# debug.net
KiCad netlist of a schematic drawn in Altium Designer
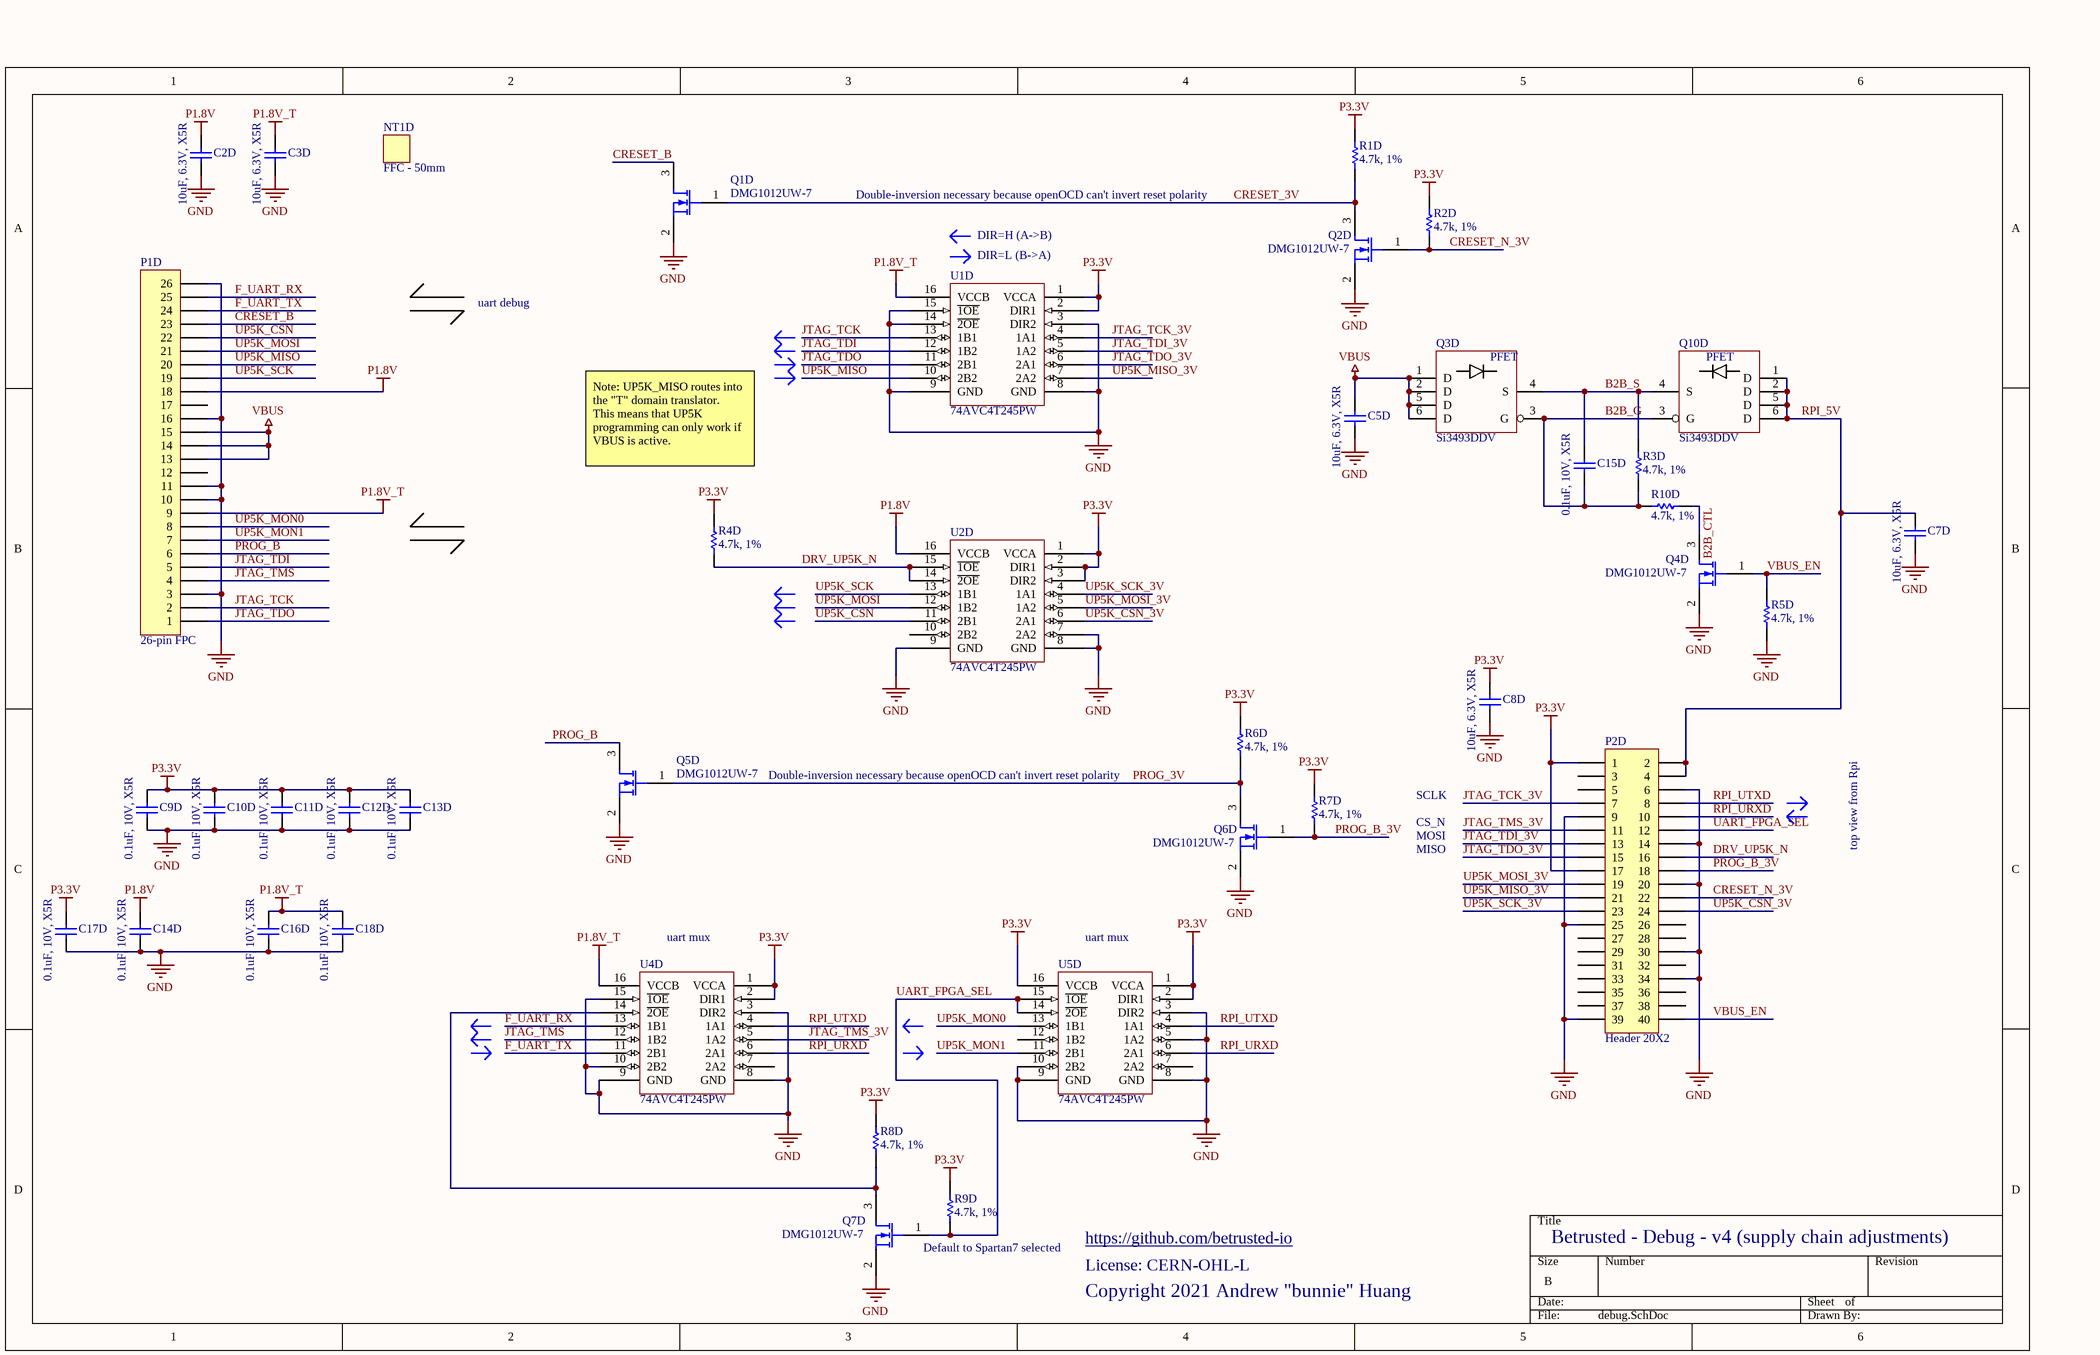
[diagram p0: debug.SchDoc]

(export (version "E")
  (design (tool "Eeschema 10.0.6"))
  (components
    (comp (ref "C2D")
      (value "10uF, 6.3V, X5R")
      (footprint "B_CAP0603")
      (description "Capacitor (Semiconductor SIM Model)")
      (fields (field (name "MPN") "CL10A106MQ8NNNC"))
      (libsource (lib "Miscellaneous Devices") (part "Cap Semi"))
    )
    (comp (ref "C3D")
      (value "10uF, 6.3V, X5R")
      (footprint "B_CAP0603")
      (description "Capacitor (Semiconductor SIM Model)")
      (fields (field (name "MPN") "CL10A106MQ8NNNC"))
      (libsource (lib "Miscellaneous Devices") (part "Cap Semi"))
    )
    (comp (ref "C5D")
      (value "10uF, 6.3V, X5R")
      (footprint "B_CAP0603")
      (description "Capacitor (Semiconductor SIM Model)")
      (fields (field (name "MPN") "CL10A106MQ8NNNC"))
      (libsource (lib "Miscellaneous Devices") (part "Cap Semi"))
    )
    (comp (ref "C7D")
      (value "10uF, 6.3V, X5R")
      (footprint "B_CAP0603")
      (description "Capacitor (Semiconductor SIM Model)")
      (fields (field (name "MPN") "CL10A106MQ8NNNC"))
      (libsource (lib "Miscellaneous Devices") (part "Cap Semi"))
    )
    (comp (ref "C8D")
      (value "10uF, 6.3V, X5R")
      (footprint "B_CAP0603")
      (description "Capacitor (Semiconductor SIM Model)")
      (fields (field (name "MPN") "CL10A106MQ8NNNC"))
      (libsource (lib "Miscellaneous Devices") (part "Cap Semi"))
    )
    (comp (ref "C9D")
      (value "0.1uF, 10V, X5R")
      (footprint "B_CAP0402")
      (description "Capacitor (Semiconductor SIM Model)")
      (fields (field (name "MPN") "CL05A104KP5NNNC"))
      (libsource (lib "Miscellaneous Devices") (part "Cap Semi"))
    )
    (comp (ref "C10D")
      (value "0.1uF, 10V, X5R")
      (footprint "B_CAP0402")
      (description "Capacitor (Semiconductor SIM Model)")
      (fields (field (name "MPN") "CL05A104KP5NNNC"))
      (libsource (lib "Miscellaneous Devices") (part "Cap Semi"))
    )
    (comp (ref "C11D")
      (value "0.1uF, 10V, X5R")
      (footprint "B_CAP0402")
      (description "Capacitor (Semiconductor SIM Model)")
      (fields (field (name "MPN") "CL05A104KP5NNNC"))
      (libsource (lib "Miscellaneous Devices") (part "Cap Semi"))
    )
    (comp (ref "C12D")
      (value "0.1uF, 10V, X5R")
      (footprint "B_CAP0402")
      (description "Capacitor (Semiconductor SIM Model)")
      (fields (field (name "MPN") "CL05A104KP5NNNC"))
      (libsource (lib "Miscellaneous Devices") (part "Cap Semi"))
    )
    (comp (ref "C13D")
      (value "0.1uF, 10V, X5R")
      (footprint "B_CAP0402")
      (description "Capacitor (Semiconductor SIM Model)")
      (fields (field (name "MPN") "CL05A104KP5NNNC"))
      (libsource (lib "Miscellaneous Devices") (part "Cap Semi"))
    )
    (comp (ref "C14D")
      (value "0.1uF, 10V, X5R")
      (footprint "B_CAP0402")
      (description "Capacitor (Semiconductor SIM Model)")
      (fields (field (name "MPN") "CL05A104KP5NNNC"))
      (libsource (lib "Miscellaneous Devices") (part "Cap Semi"))
    )
    (comp (ref "C15D")
      (value "0.1uF, 10V, X5R")
      (footprint "B_CAP0402")
      (description "Capacitor (Semiconductor SIM Model)")
      (fields (field (name "MPN") "CL05A104KP5NNNC"))
      (libsource (lib "Miscellaneous Devices") (part "Cap Semi"))
    )
    (comp (ref "C16D")
      (value "0.1uF, 10V, X5R")
      (footprint "B_CAP0402")
      (description "Capacitor (Semiconductor SIM Model)")
      (fields (field (name "MPN") "CL05A104KP5NNNC"))
      (libsource (lib "Miscellaneous Devices") (part "Cap Semi"))
    )
    (comp (ref "C17D")
      (value "0.1uF, 10V, X5R")
      (footprint "B_CAP0402")
      (description "Capacitor (Semiconductor SIM Model)")
      (fields (field (name "MPN") "CL05A104KP5NNNC"))
      (libsource (lib "Miscellaneous Devices") (part "Cap Semi"))
    )
    (comp (ref "C18D")
      (value "0.1uF, 10V, X5R")
      (footprint "B_CAP0402")
      (description "Capacitor (Semiconductor SIM Model)")
      (fields (field (name "MPN") "CL05A104KP5NNNC"))
      (libsource (lib "Miscellaneous Devices") (part "Cap Semi"))
    )
    (comp (ref "NT1D")
      (value "FFC - 50mm")
      (description "Placeholder for non-board BOM items")
      (fields (field (name "MPN") "FJH-26-D-02.00-4"))
      (libsource (lib "commonsch") (part "NOTE"))
    )
    (comp (ref "P1D")
      (value "26-pin FPC")
      (footprint "HRS_FH34SRJ-26S-0.5SH(50)")
      (description "26 Pin FPC header")
      (fields (field (name "MPN") "FH34SRJ-26S-0.5SH(99)"))
      (libsource (lib "commonsch-new") (part "FPC-26"))
    )
    (comp (ref "P2D")
      (value "Header 20X2")
      (footprint "SAMTEC_SSW-120-01-F-D")
      (description "Header, 20-Pin, Dual row")
      (fields (field (name "MPN") "CS25402-40G-S85-C") (field (name "PUBLISHER") "Altium Limited"))
      (libsource (lib "Miscellaneous Connectors") (part "Header 20X2"))
    )
    (comp (ref "Q1D")
      (value "DMG1012UW-7")
      (footprint "SOT323-3AN")
      (description "N-Channel MOSFET")
      (fields (field (name "PUBLISHER") "Altium Limited"))
      (libsource (lib "Miscellaneous Devices") (part "MOSFET-N"))
    )
    (comp (ref "Q2D")
      (value "DMG1012UW-7")
      (footprint "SOT323-3AN")
      (description "N-Channel MOSFET")
      (fields (field (name "PUBLISHER") "Altium Limited"))
      (libsource (lib "Miscellaneous Devices") (part "MOSFET-N"))
    )
    (comp (ref "Q3D")
      (value "Si3493DDV")
      (footprint "SOT26A-6N")
      (description "P-channel 20V 8A 32mOhm @ -2.5V")
      (fields (field (name "MPN") "SI3493DDV-T1-GE3"))
      (libsource (lib "") (part "Si3493DDV_1"))
    )
    (comp (ref "Q4D")
      (value "DMG1012UW-7")
      (footprint "SOT323-3AN")
      (description "N-Channel MOSFET")
      (fields (field (name "PUBLISHER") "Altium Limited"))
      (libsource (lib "Miscellaneous Devices") (part "MOSFET-N"))
    )
    (comp (ref "Q5D")
      (value "DMG1012UW-7")
      (footprint "SOT323-3AN")
      (description "N-Channel MOSFET")
      (fields (field (name "PUBLISHER") "Altium Limited"))
      (libsource (lib "Miscellaneous Devices") (part "MOSFET-N"))
    )
    (comp (ref "Q6D")
      (value "DMG1012UW-7")
      (footprint "SOT323-3AN")
      (description "N-Channel MOSFET")
      (fields (field (name "PUBLISHER") "Altium Limited"))
      (libsource (lib "Miscellaneous Devices") (part "MOSFET-N"))
    )
    (comp (ref "Q7D")
      (value "DMG1012UW-7")
      (footprint "SOT323-3AN")
      (description "N-Channel MOSFET")
      (fields (field (name "PUBLISHER") "Altium Limited"))
      (libsource (lib "Miscellaneous Devices") (part "MOSFET-N"))
    )
    (comp (ref "Q10D")
      (value "Si3493DDV")
      (footprint "SOT26A-6N")
      (description "P-channel 20V 8A 32mOhm @ -2.5V")
      (fields (field (name "MPN") "SI3493DDV-T1-GE3"))
      (libsource (lib "commonsch-new") (part "Si3493DDV"))
    )
    (comp (ref "R1D")
      (value "4.7k, 1%")
      (footprint "B_RES0402")
      (description "Resistor")
      (fields (field (name "MPN") "ANY"))
      (libsource (lib "Miscellaneous Devices") (part "Res1"))
    )
    (comp (ref "R2D")
      (value "4.7k, 1%")
      (footprint "B_RES0402")
      (description "Resistor")
      (fields (field (name "MPN") "ANY"))
      (libsource (lib "Miscellaneous Devices") (part "Res1"))
    )
    (comp (ref "R3D")
      (value "4.7k, 1%")
      (footprint "B_RES0402")
      (description "Resistor")
      (fields (field (name "MPN") "ANY"))
      (libsource (lib "Miscellaneous Devices") (part "Res1"))
    )
    (comp (ref "R4D")
      (value "4.7k, 1%")
      (footprint "B_RES0402")
      (description "Resistor")
      (fields (field (name "MPN") "ANY"))
      (libsource (lib "Miscellaneous Devices") (part "Res1"))
    )
    (comp (ref "R5D")
      (value "4.7k, 1%")
      (footprint "B_RES0402")
      (description "Resistor")
      (fields (field (name "MPN") "ANY"))
      (libsource (lib "Miscellaneous Devices") (part "Res1"))
    )
    (comp (ref "R6D")
      (value "4.7k, 1%")
      (footprint "B_RES0402")
      (description "Resistor")
      (fields (field (name "MPN") "ANY"))
      (libsource (lib "Miscellaneous Devices") (part "Res1"))
    )
    (comp (ref "R7D")
      (value "4.7k, 1%")
      (footprint "B_RES0402")
      (description "Resistor")
      (fields (field (name "MPN") "ANY"))
      (libsource (lib "Miscellaneous Devices") (part "Res1"))
    )
    (comp (ref "R8D")
      (value "4.7k, 1%")
      (footprint "B_RES0402")
      (description "Resistor")
      (fields (field (name "MPN") "ANY"))
      (libsource (lib "Miscellaneous Devices") (part "Res1"))
    )
    (comp (ref "R9D")
      (value "4.7k, 1%")
      (footprint "B_RES0402")
      (description "Resistor")
      (fields (field (name "MPN") "ANY"))
      (libsource (lib "Miscellaneous Devices") (part "Res1"))
    )
    (comp (ref "R10D")
      (value "4.7k, 1%")
      (footprint "B_RES0402")
      (description "Resistor")
      (fields (field (name "MPN") "ANY"))
      (libsource (lib "Miscellaneous Devices") (part "Res1"))
    )
    (comp (ref "U1D")
      (value "74AVC4T245PW")
      (footprint "TSOP65P640-16AN")
      (libsource (lib "commonsch-new") (part "74AVC4T245"))
    )
    (comp (ref "U2D")
      (value "74AVC4T245PW")
      (footprint "TSOP65P640-16AN")
      (libsource (lib "commonsch-new") (part "74AVC4T245"))
    )
    (comp (ref "U4D")
      (value "74AVC4T245PW")
      (footprint "TSOP65P640-16AN")
      (libsource (lib "commonsch-new") (part "74AVC4T245"))
    )
    (comp (ref "U5D")
      (value "74AVC4T245PW")
      (footprint "TSOP65P640-16AN")
      (libsource (lib "commonsch-new") (part "74AVC4T245"))
    )
  )
  (nets
    (net (code "1") (name "/B2B_CTL") (class "Default")
      (node (ref "Q4D") (pin "3") (pinfunction "D_3") (pintype "passive"))
      (node (ref "R10D") (pin "2") (pinfunction "2_2") (pintype "passive"))
    )
    (net (code "2") (name "/B2B_G") (class "Default")
      (node (ref "C15D") (pin "2") (pinfunction "2_2") (pintype "passive"))
      (node (ref "Q10D") (pin "3") (pinfunction "G_3") (pintype "passive"))
      (node (ref "Q3D") (pin "3") (pinfunction "G_3") (pintype "passive"))
      (node (ref "R10D") (pin "1") (pinfunction "1_1") (pintype "passive"))
      (node (ref "R3D") (pin "2") (pinfunction "2_2") (pintype "passive"))
    )
    (net (code "3") (name "/B2B_S") (class "Default")
      (node (ref "C15D") (pin "1") (pinfunction "1_1") (pintype "passive"))
      (node (ref "Q10D") (pin "4") (pinfunction "S_4") (pintype "passive"))
      (node (ref "Q3D") (pin "4") (pinfunction "S_4") (pintype "passive"))
      (node (ref "R3D") (pin "1") (pinfunction "1_1") (pintype "passive"))
    )
    (net (code "4") (name "/CRESET_3V") (class "Default")
      (node (ref "Q1D") (pin "1") (pinfunction "G_1") (pintype "passive"))
      (node (ref "Q2D") (pin "3") (pinfunction "D_3") (pintype "passive"))
      (node (ref "R1D") (pin "1") (pinfunction "1_1") (pintype "passive"))
    )
    (net (code "5") (name "/CRESET_B") (class "Default")
      (node (ref "P1D") (pin "23") (pinfunction "23_23") (pintype "passive"))
      (node (ref "Q1D") (pin "3") (pinfunction "D_3") (pintype "passive"))
    )
    (net (code "6") (name "/CRESET_N_3V") (class "Default")
      (node (ref "P2D") (pin "22") (pinfunction "22_22") (pintype "passive"))
      (node (ref "Q2D") (pin "1") (pinfunction "G_1") (pintype "passive"))
      (node (ref "R2D") (pin "1") (pinfunction "1_1") (pintype "passive"))
    )
    (net (code "7") (name "/DRV_UP5K_N") (class "Default")
      (node (ref "P2D") (pin "16") (pinfunction "16_16") (pintype "passive"))
      (node (ref "R4D") (pin "1") (pinfunction "1_1") (pintype "passive"))
      (node (ref "U2D") (pin "14") (pinfunction "~{2OE}_14") (pintype "input"))
      (node (ref "U2D") (pin "15") (pinfunction "~{1OE}_15") (pintype "input"))
    )
    (net (code "8") (name "/F_UART_RX") (class "Default")
      (node (ref "P1D") (pin "25") (pinfunction "25_25") (pintype "passive"))
      (node (ref "U4D") (pin "13") (pinfunction "1B1_13") (pintype "bidirectional"))
    )
    (net (code "9") (name "/F_UART_TX") (class "Default")
      (node (ref "P1D") (pin "24") (pinfunction "24_24") (pintype "passive"))
      (node (ref "U4D") (pin "11") (pinfunction "2B1_11") (pintype "bidirectional"))
    )
    (net (code "10") (name "/JTAG_TCK") (class "Default")
      (node (ref "P1D") (pin "2") (pinfunction "2_2") (pintype "passive"))
      (node (ref "U1D") (pin "13") (pinfunction "1B1_13") (pintype "bidirectional"))
    )
    (net (code "11") (name "/JTAG_TCK_3V") (class "Default")
      (node (ref "P2D") (pin "7") (pinfunction "7_7") (pintype "passive"))
      (node (ref "U1D") (pin "4") (pinfunction "1A1_4") (pintype "bidirectional"))
    )
    (net (code "12") (name "/JTAG_TDI") (class "Default")
      (node (ref "P1D") (pin "5") (pinfunction "5_5") (pintype "passive"))
      (node (ref "U1D") (pin "12") (pinfunction "1B2_12") (pintype "bidirectional"))
    )
    (net (code "13") (name "/JTAG_TDI_3V") (class "Default")
      (node (ref "P2D") (pin "13") (pinfunction "13_13") (pintype "passive"))
      (node (ref "U1D") (pin "5") (pinfunction "1A2_5") (pintype "bidirectional"))
    )
    (net (code "14") (name "/JTAG_TDO") (class "Default")
      (node (ref "P1D") (pin "1") (pinfunction "1_1") (pintype "passive"))
      (node (ref "U1D") (pin "11") (pinfunction "2B1_11") (pintype "bidirectional"))
    )
    (net (code "15") (name "/JTAG_TDO_3V") (class "Default")
      (node (ref "P2D") (pin "15") (pinfunction "15_15") (pintype "passive"))
      (node (ref "U1D") (pin "6") (pinfunction "2A1_6") (pintype "bidirectional"))
    )
    (net (code "16") (name "/JTAG_TMS") (class "Default")
      (node (ref "P1D") (pin "4") (pinfunction "4_4") (pintype "passive"))
      (node (ref "U4D") (pin "12") (pinfunction "1B2_12") (pintype "bidirectional"))
    )
    (net (code "17") (name "/JTAG_TMS_3V") (class "Default")
      (node (ref "P2D") (pin "11") (pinfunction "11_11") (pintype "passive"))
      (node (ref "U4D") (pin "5") (pinfunction "1A2_5") (pintype "bidirectional"))
    )
    (net (code "18") (name "/PROG_3V") (class "Default")
      (node (ref "Q5D") (pin "1") (pinfunction "G_1") (pintype "passive"))
      (node (ref "Q6D") (pin "3") (pinfunction "D_3") (pintype "passive"))
      (node (ref "R6D") (pin "1") (pinfunction "1_1") (pintype "passive"))
    )
    (net (code "19") (name "/PROG_B") (class "Default")
      (node (ref "P1D") (pin "6") (pinfunction "6_6") (pintype "passive"))
      (node (ref "Q5D") (pin "3") (pinfunction "D_3") (pintype "passive"))
    )
    (net (code "20") (name "/PROG_B_3V") (class "Default")
      (node (ref "P2D") (pin "18") (pinfunction "18_18") (pintype "passive"))
      (node (ref "Q6D") (pin "1") (pinfunction "G_1") (pintype "passive"))
      (node (ref "R7D") (pin "1") (pinfunction "1_1") (pintype "passive"))
    )
    (net (code "21") (name "/RPI_5V") (class "Default")
      (node (ref "C7D") (pin "1") (pinfunction "1_1") (pintype "passive"))
      (node (ref "P2D") (pin "2") (pinfunction "2_2") (pintype "passive"))
      (node (ref "P2D") (pin "4") (pinfunction "4_4") (pintype "passive"))
      (node (ref "Q10D") (pin "1") (pinfunction "D_1") (pintype "passive"))
      (node (ref "Q10D") (pin "2") (pinfunction "D_2") (pintype "passive"))
      (node (ref "Q10D") (pin "5") (pinfunction "D_5") (pintype "passive"))
      (node (ref "Q10D") (pin "6") (pinfunction "D_6") (pintype "passive"))
    )
    (net (code "22") (name "/RPI_URXD") (class "Default")
      (node (ref "P2D") (pin "10") (pinfunction "10_10") (pintype "passive"))
      (node (ref "U4D") (pin "6") (pinfunction "2A1_6") (pintype "bidirectional"))
      (node (ref "U5D") (pin "6") (pinfunction "2A1_6") (pintype "bidirectional"))
    )
    (net (code "23") (name "/RPI_UTXD") (class "Default")
      (node (ref "P2D") (pin "8") (pinfunction "8_8") (pintype "passive"))
      (node (ref "U4D") (pin "4") (pinfunction "1A1_4") (pintype "bidirectional"))
      (node (ref "U5D") (pin "4") (pinfunction "1A1_4") (pintype "bidirectional"))
    )
    (net (code "24") (name "/UART_FPGA_SEL") (class "Default")
      (node (ref "P2D") (pin "12") (pinfunction "12_12") (pintype "passive"))
      (node (ref "Q7D") (pin "1") (pinfunction "G_1") (pintype "passive"))
      (node (ref "R9D") (pin "1") (pinfunction "1_1") (pintype "passive"))
      (node (ref "U5D") (pin "14") (pinfunction "~{2OE}_14") (pintype "input"))
      (node (ref "U5D") (pin "15") (pinfunction "~{1OE}_15") (pintype "input"))
    )
    (net (code "25") (name "/UP5K_CSN") (class "Default")
      (node (ref "P1D") (pin "22") (pinfunction "22_22") (pintype "passive"))
      (node (ref "U2D") (pin "11") (pinfunction "2B1_11") (pintype "bidirectional"))
    )
    (net (code "26") (name "/UP5K_CSN_3V") (class "Default")
      (node (ref "P2D") (pin "24") (pinfunction "24_24") (pintype "passive"))
      (node (ref "U2D") (pin "6") (pinfunction "2A1_6") (pintype "bidirectional"))
    )
    (net (code "27") (name "/UP5K_MISO") (class "Default")
      (node (ref "P1D") (pin "20") (pinfunction "20_20") (pintype "passive"))
      (node (ref "U1D") (pin "10") (pinfunction "2B2_10") (pintype "bidirectional"))
    )
    (net (code "28") (name "/UP5K_MISO_3V") (class "Default")
      (node (ref "P2D") (pin "21") (pinfunction "21_21") (pintype "passive"))
      (node (ref "U1D") (pin "7") (pinfunction "2A2_7") (pintype "bidirectional"))
    )
    (net (code "29") (name "/UP5K_MON0") (class "Default")
      (node (ref "P1D") (pin "8") (pinfunction "8_8") (pintype "passive"))
      (node (ref "U5D") (pin "13") (pinfunction "1B1_13") (pintype "bidirectional"))
    )
    (net (code "30") (name "/UP5K_MON1") (class "Default")
      (node (ref "P1D") (pin "7") (pinfunction "7_7") (pintype "passive"))
      (node (ref "U5D") (pin "11") (pinfunction "2B1_11") (pintype "bidirectional"))
    )
    (net (code "31") (name "/UP5K_MOSI") (class "Default")
      (node (ref "P1D") (pin "21") (pinfunction "21_21") (pintype "passive"))
      (node (ref "U2D") (pin "12") (pinfunction "1B2_12") (pintype "bidirectional"))
    )
    (net (code "32") (name "/UP5K_MOSI_3V") (class "Default")
      (node (ref "P2D") (pin "19") (pinfunction "19_19") (pintype "passive"))
      (node (ref "U2D") (pin "5") (pinfunction "1A2_5") (pintype "bidirectional"))
    )
    (net (code "33") (name "/UP5K_SCK") (class "Default")
      (node (ref "P1D") (pin "19") (pinfunction "19_19") (pintype "passive"))
      (node (ref "U2D") (pin "13") (pinfunction "1B1_13") (pintype "bidirectional"))
    )
    (net (code "34") (name "/UP5K_SCK_3V") (class "Default")
      (node (ref "P2D") (pin "23") (pinfunction "23_23") (pintype "passive"))
      (node (ref "U2D") (pin "4") (pinfunction "1A1_4") (pintype "bidirectional"))
    )
    (net (code "35") (name "/VBUS_EN") (class "Default")
      (node (ref "P2D") (pin "40") (pinfunction "40_40") (pintype "passive"))
      (node (ref "Q4D") (pin "1") (pinfunction "G_1") (pintype "passive"))
      (node (ref "R5D") (pin "2") (pinfunction "2_2") (pintype "passive"))
    )
    (net (code "36") (name "GND") (class "Default")
      (node (ref "C10D") (pin "2") (pinfunction "2_2") (pintype "passive"))
      (node (ref "C11D") (pin "2") (pinfunction "2_2") (pintype "passive"))
      (node (ref "C12D") (pin "2") (pinfunction "2_2") (pintype "passive"))
      (node (ref "C13D") (pin "2") (pinfunction "2_2") (pintype "passive"))
      (node (ref "C14D") (pin "2") (pinfunction "2_2") (pintype "passive"))
      (node (ref "C16D") (pin "2") (pinfunction "2_2") (pintype "passive"))
      (node (ref "C17D") (pin "2") (pinfunction "2_2") (pintype "passive"))
      (node (ref "C18D") (pin "2") (pinfunction "2_2") (pintype "passive"))
      (node (ref "C2D") (pin "2") (pinfunction "2_2") (pintype "passive"))
      (node (ref "C3D") (pin "2") (pinfunction "2_2") (pintype "passive"))
      (node (ref "C5D") (pin "2") (pinfunction "2_2") (pintype "passive"))
      (node (ref "C7D") (pin "2") (pinfunction "2_2") (pintype "passive"))
      (node (ref "C8D") (pin "2") (pinfunction "2_2") (pintype "passive"))
      (node (ref "C9D") (pin "2") (pinfunction "2_2") (pintype "passive"))
      (node (ref "P1D") (pin "10") (pinfunction "10_10") (pintype "passive"))
      (node (ref "P1D") (pin "11") (pinfunction "11_11") (pintype "passive"))
      (node (ref "P1D") (pin "16") (pinfunction "16_16") (pintype "passive"))
      (node (ref "P1D") (pin "26") (pinfunction "26_26") (pintype "passive"))
      (node (ref "P1D") (pin "3") (pinfunction "3_3") (pintype "passive"))
      (node (ref "P2D") (pin "14") (pinfunction "14_14") (pintype "passive"))
      (node (ref "P2D") (pin "20") (pinfunction "20_20") (pintype "passive"))
      (node (ref "P2D") (pin "25") (pinfunction "25_25") (pintype "passive"))
      (node (ref "P2D") (pin "30") (pinfunction "30_30") (pintype "passive"))
      (node (ref "P2D") (pin "34") (pinfunction "34_34") (pintype "passive"))
      (node (ref "P2D") (pin "39") (pinfunction "39_39") (pintype "passive"))
      (node (ref "P2D") (pin "6") (pinfunction "6_6") (pintype "passive"))
      (node (ref "P2D") (pin "9") (pinfunction "9_9") (pintype "passive"))
      (node (ref "Q1D") (pin "2") (pinfunction "S_2") (pintype "passive"))
      (node (ref "Q2D") (pin "2") (pinfunction "S_2") (pintype "passive"))
      (node (ref "Q4D") (pin "2") (pinfunction "S_2") (pintype "passive"))
      (node (ref "Q5D") (pin "2") (pinfunction "S_2") (pintype "passive"))
      (node (ref "Q6D") (pin "2") (pinfunction "S_2") (pintype "passive"))
      (node (ref "Q7D") (pin "2") (pinfunction "S_2") (pintype "passive"))
      (node (ref "R5D") (pin "1") (pinfunction "1_1") (pintype "passive"))
      (node (ref "U1D") (pin "14") (pinfunction "~{2OE}_14") (pintype "input"))
      (node (ref "U1D") (pin "15") (pinfunction "~{1OE}_15") (pintype "input"))
      (node (ref "U1D") (pin "3") (pinfunction "DIR2_3") (pintype "input"))
      (node (ref "U1D") (pin "8") (pinfunction "GND_8") (pintype "power_in"))
      (node (ref "U1D") (pin "9") (pinfunction "GND_9") (pintype "power_in"))
      (node (ref "U2D") (pin "7") (pinfunction "2A2_7") (pintype "bidirectional"))
      (node (ref "U2D") (pin "8") (pinfunction "GND_8") (pintype "power_in"))
      (node (ref "U2D") (pin "9") (pinfunction "GND_9") (pintype "power_in"))
      (node (ref "U4D") (pin "10") (pinfunction "2B2_10") (pintype "bidirectional"))
      (node (ref "U4D") (pin "15") (pinfunction "~{1OE}_15") (pintype "input"))
      (node (ref "U4D") (pin "3") (pinfunction "DIR2_3") (pintype "input"))
      (node (ref "U4D") (pin "8") (pinfunction "GND_8") (pintype "power_in"))
      (node (ref "U4D") (pin "9") (pinfunction "GND_9") (pintype "power_in"))
      (node (ref "U5D") (pin "10") (pinfunction "2B2_10") (pintype "bidirectional"))
      (node (ref "U5D") (pin "3") (pinfunction "DIR2_3") (pintype "input"))
      (node (ref "U5D") (pin "5") (pinfunction "1A2_5") (pintype "bidirectional"))
      (node (ref "U5D") (pin "8") (pinfunction "GND_8") (pintype "power_in"))
      (node (ref "U5D") (pin "9") (pinfunction "GND_9") (pintype "power_in"))
    )
    (net (code "37") (name "Net-(Q7D-D)") (class "Default")
      (node (ref "Q7D") (pin "3") (pinfunction "D_3") (pintype "passive"))
      (node (ref "R8D") (pin "1") (pinfunction "1_1") (pintype "passive"))
      (node (ref "U4D") (pin "14") (pinfunction "~{2OE}_14") (pintype "input"))
    )
    (net (code "38") (name "P1.8V") (class "Default")
      (node (ref "C14D") (pin "1") (pinfunction "1_1") (pintype "passive"))
      (node (ref "C2D") (pin "1") (pinfunction "1_1") (pintype "passive"))
      (node (ref "P1D") (pin "18") (pinfunction "18_18") (pintype "passive"))
      (node (ref "U2D") (pin "16") (pinfunction "VCCB_16") (pintype "power_in"))
    )
    (net (code "39") (name "P1.8V_T") (class "Default")
      (node (ref "C16D") (pin "1") (pinfunction "1_1") (pintype "passive"))
      (node (ref "C18D") (pin "1") (pinfunction "1_1") (pintype "passive"))
      (node (ref "C3D") (pin "1") (pinfunction "1_1") (pintype "passive"))
      (node (ref "P1D") (pin "9") (pinfunction "9_9") (pintype "passive"))
      (node (ref "U1D") (pin "16") (pinfunction "VCCB_16") (pintype "power_in"))
      (node (ref "U4D") (pin "16") (pinfunction "VCCB_16") (pintype "power_in"))
    )
    (net (code "40") (name "P3.3V") (class "Default")
      (node (ref "C10D") (pin "1") (pinfunction "1_1") (pintype "passive"))
      (node (ref "C11D") (pin "1") (pinfunction "1_1") (pintype "passive"))
      (node (ref "C12D") (pin "1") (pinfunction "1_1") (pintype "passive"))
      (node (ref "C13D") (pin "1") (pinfunction "1_1") (pintype "passive"))
      (node (ref "C17D") (pin "1") (pinfunction "1_1") (pintype "passive"))
      (node (ref "C8D") (pin "1") (pinfunction "1_1") (pintype "passive"))
      (node (ref "C9D") (pin "1") (pinfunction "1_1") (pintype "passive"))
      (node (ref "P2D") (pin "1") (pinfunction "1_1") (pintype "passive"))
      (node (ref "P2D") (pin "17") (pinfunction "17_17") (pintype "passive"))
      (node (ref "R1D") (pin "2") (pinfunction "2_2") (pintype "passive"))
      (node (ref "R2D") (pin "2") (pinfunction "2_2") (pintype "passive"))
      (node (ref "R4D") (pin "2") (pinfunction "2_2") (pintype "passive"))
      (node (ref "R6D") (pin "2") (pinfunction "2_2") (pintype "passive"))
      (node (ref "R7D") (pin "2") (pinfunction "2_2") (pintype "passive"))
      (node (ref "R8D") (pin "2") (pinfunction "2_2") (pintype "passive"))
      (node (ref "R9D") (pin "2") (pinfunction "2_2") (pintype "passive"))
      (node (ref "U1D") (pin "1") (pinfunction "VCCA_1") (pintype "power_in"))
      (node (ref "U1D") (pin "2") (pinfunction "DIR1_2") (pintype "input"))
      (node (ref "U2D") (pin "1") (pinfunction "VCCA_1") (pintype "power_in"))
      (node (ref "U2D") (pin "2") (pinfunction "DIR1_2") (pintype "input"))
      (node (ref "U2D") (pin "3") (pinfunction "DIR2_3") (pintype "input"))
      (node (ref "U4D") (pin "1") (pinfunction "VCCA_1") (pintype "power_in"))
      (node (ref "U4D") (pin "2") (pinfunction "DIR1_2") (pintype "input"))
      (node (ref "U5D") (pin "1") (pinfunction "VCCA_1") (pintype "power_in"))
      (node (ref "U5D") (pin "16") (pinfunction "VCCB_16") (pintype "power_in"))
      (node (ref "U5D") (pin "2") (pinfunction "DIR1_2") (pintype "input"))
    )
    (net (code "41") (name "VBUS") (class "Default")
      (node (ref "C5D") (pin "1") (pinfunction "1_1") (pintype "passive"))
      (node (ref "P1D") (pin "13") (pinfunction "13_13") (pintype "passive"))
      (node (ref "P1D") (pin "14") (pinfunction "14_14") (pintype "passive"))
      (node (ref "P1D") (pin "15") (pinfunction "15_15") (pintype "passive"))
      (node (ref "Q3D") (pin "1") (pinfunction "D_1") (pintype "passive"))
      (node (ref "Q3D") (pin "2") (pinfunction "D_2") (pintype "passive"))
      (node (ref "Q3D") (pin "5") (pinfunction "D_5") (pintype "passive"))
      (node (ref "Q3D") (pin "6") (pinfunction "D_6") (pintype "passive"))
    )
    (net (code "42") (name "unconnected-(P1D-Pad12)") (class "Default")
      (node (ref "P1D") (pin "12") (pinfunction "12_12") (pintype "passive"))
    )
    (net (code "43") (name "unconnected-(P1D-Pad17)") (class "Default")
      (node (ref "P1D") (pin "17") (pinfunction "17_17") (pintype "passive"))
    )
    (net (code "44") (name "unconnected-(P2D-Pad3)") (class "Default")
      (node (ref "P2D") (pin "3") (pinfunction "3_3") (pintype "passive"))
    )
    (net (code "45") (name "unconnected-(P2D-Pad5)") (class "Default")
      (node (ref "P2D") (pin "5") (pinfunction "5_5") (pintype "passive"))
    )
    (net (code "46") (name "unconnected-(P2D-Pad26)") (class "Default")
      (node (ref "P2D") (pin "26") (pinfunction "26_26") (pintype "passive"))
    )
    (net (code "47") (name "unconnected-(P2D-Pad27)") (class "Default")
      (node (ref "P2D") (pin "27") (pinfunction "27_27") (pintype "passive"))
    )
    (net (code "48") (name "unconnected-(P2D-Pad28)") (class "Default")
      (node (ref "P2D") (pin "28") (pinfunction "28_28") (pintype "passive"))
    )
    (net (code "49") (name "unconnected-(P2D-Pad29)") (class "Default")
      (node (ref "P2D") (pin "29") (pinfunction "29_29") (pintype "passive"))
    )
    (net (code "50") (name "unconnected-(P2D-Pad31)") (class "Default")
      (node (ref "P2D") (pin "31") (pinfunction "31_31") (pintype "passive"))
    )
    (net (code "51") (name "unconnected-(P2D-Pad32)") (class "Default")
      (node (ref "P2D") (pin "32") (pinfunction "32_32") (pintype "passive"))
    )
    (net (code "52") (name "unconnected-(P2D-Pad33)") (class "Default")
      (node (ref "P2D") (pin "33") (pinfunction "33_33") (pintype "passive"))
    )
    (net (code "53") (name "unconnected-(P2D-Pad35)") (class "Default")
      (node (ref "P2D") (pin "35") (pinfunction "35_35") (pintype "passive"))
    )
    (net (code "54") (name "unconnected-(P2D-Pad36)") (class "Default")
      (node (ref "P2D") (pin "36") (pinfunction "36_36") (pintype "passive"))
    )
    (net (code "55") (name "unconnected-(P2D-Pad37)") (class "Default")
      (node (ref "P2D") (pin "37") (pinfunction "37_37") (pintype "passive"))
    )
    (net (code "56") (name "unconnected-(P2D-Pad38)") (class "Default")
      (node (ref "P2D") (pin "38") (pinfunction "38_38") (pintype "passive"))
    )
    (net (code "57") (name "unconnected-(U2D-2B2-Pad10)") (class "Default")
      (node (ref "U2D") (pin "10") (pinfunction "2B2_10") (pintype "bidirectional"))
    )
    (net (code "58") (name "unconnected-(U4D-2A2-Pad7)") (class "Default")
      (node (ref "U4D") (pin "7") (pinfunction "2A2_7") (pintype "bidirectional"))
    )
    (net (code "59") (name "unconnected-(U5D-1B2-Pad12)") (class "Default")
      (node (ref "U5D") (pin "12") (pinfunction "1B2_12") (pintype "bidirectional"))
    )
    (net (code "60") (name "unconnected-(U5D-2A2-Pad7)") (class "Default")
      (node (ref "U5D") (pin "7") (pinfunction "2A2_7") (pintype "bidirectional"))
    )
  )
)
